# ProPrj_W51F6240S16_DEVB_V2_2026-07-19.net
KiCad netlist of a schematic drawn in EasyEDA Pro
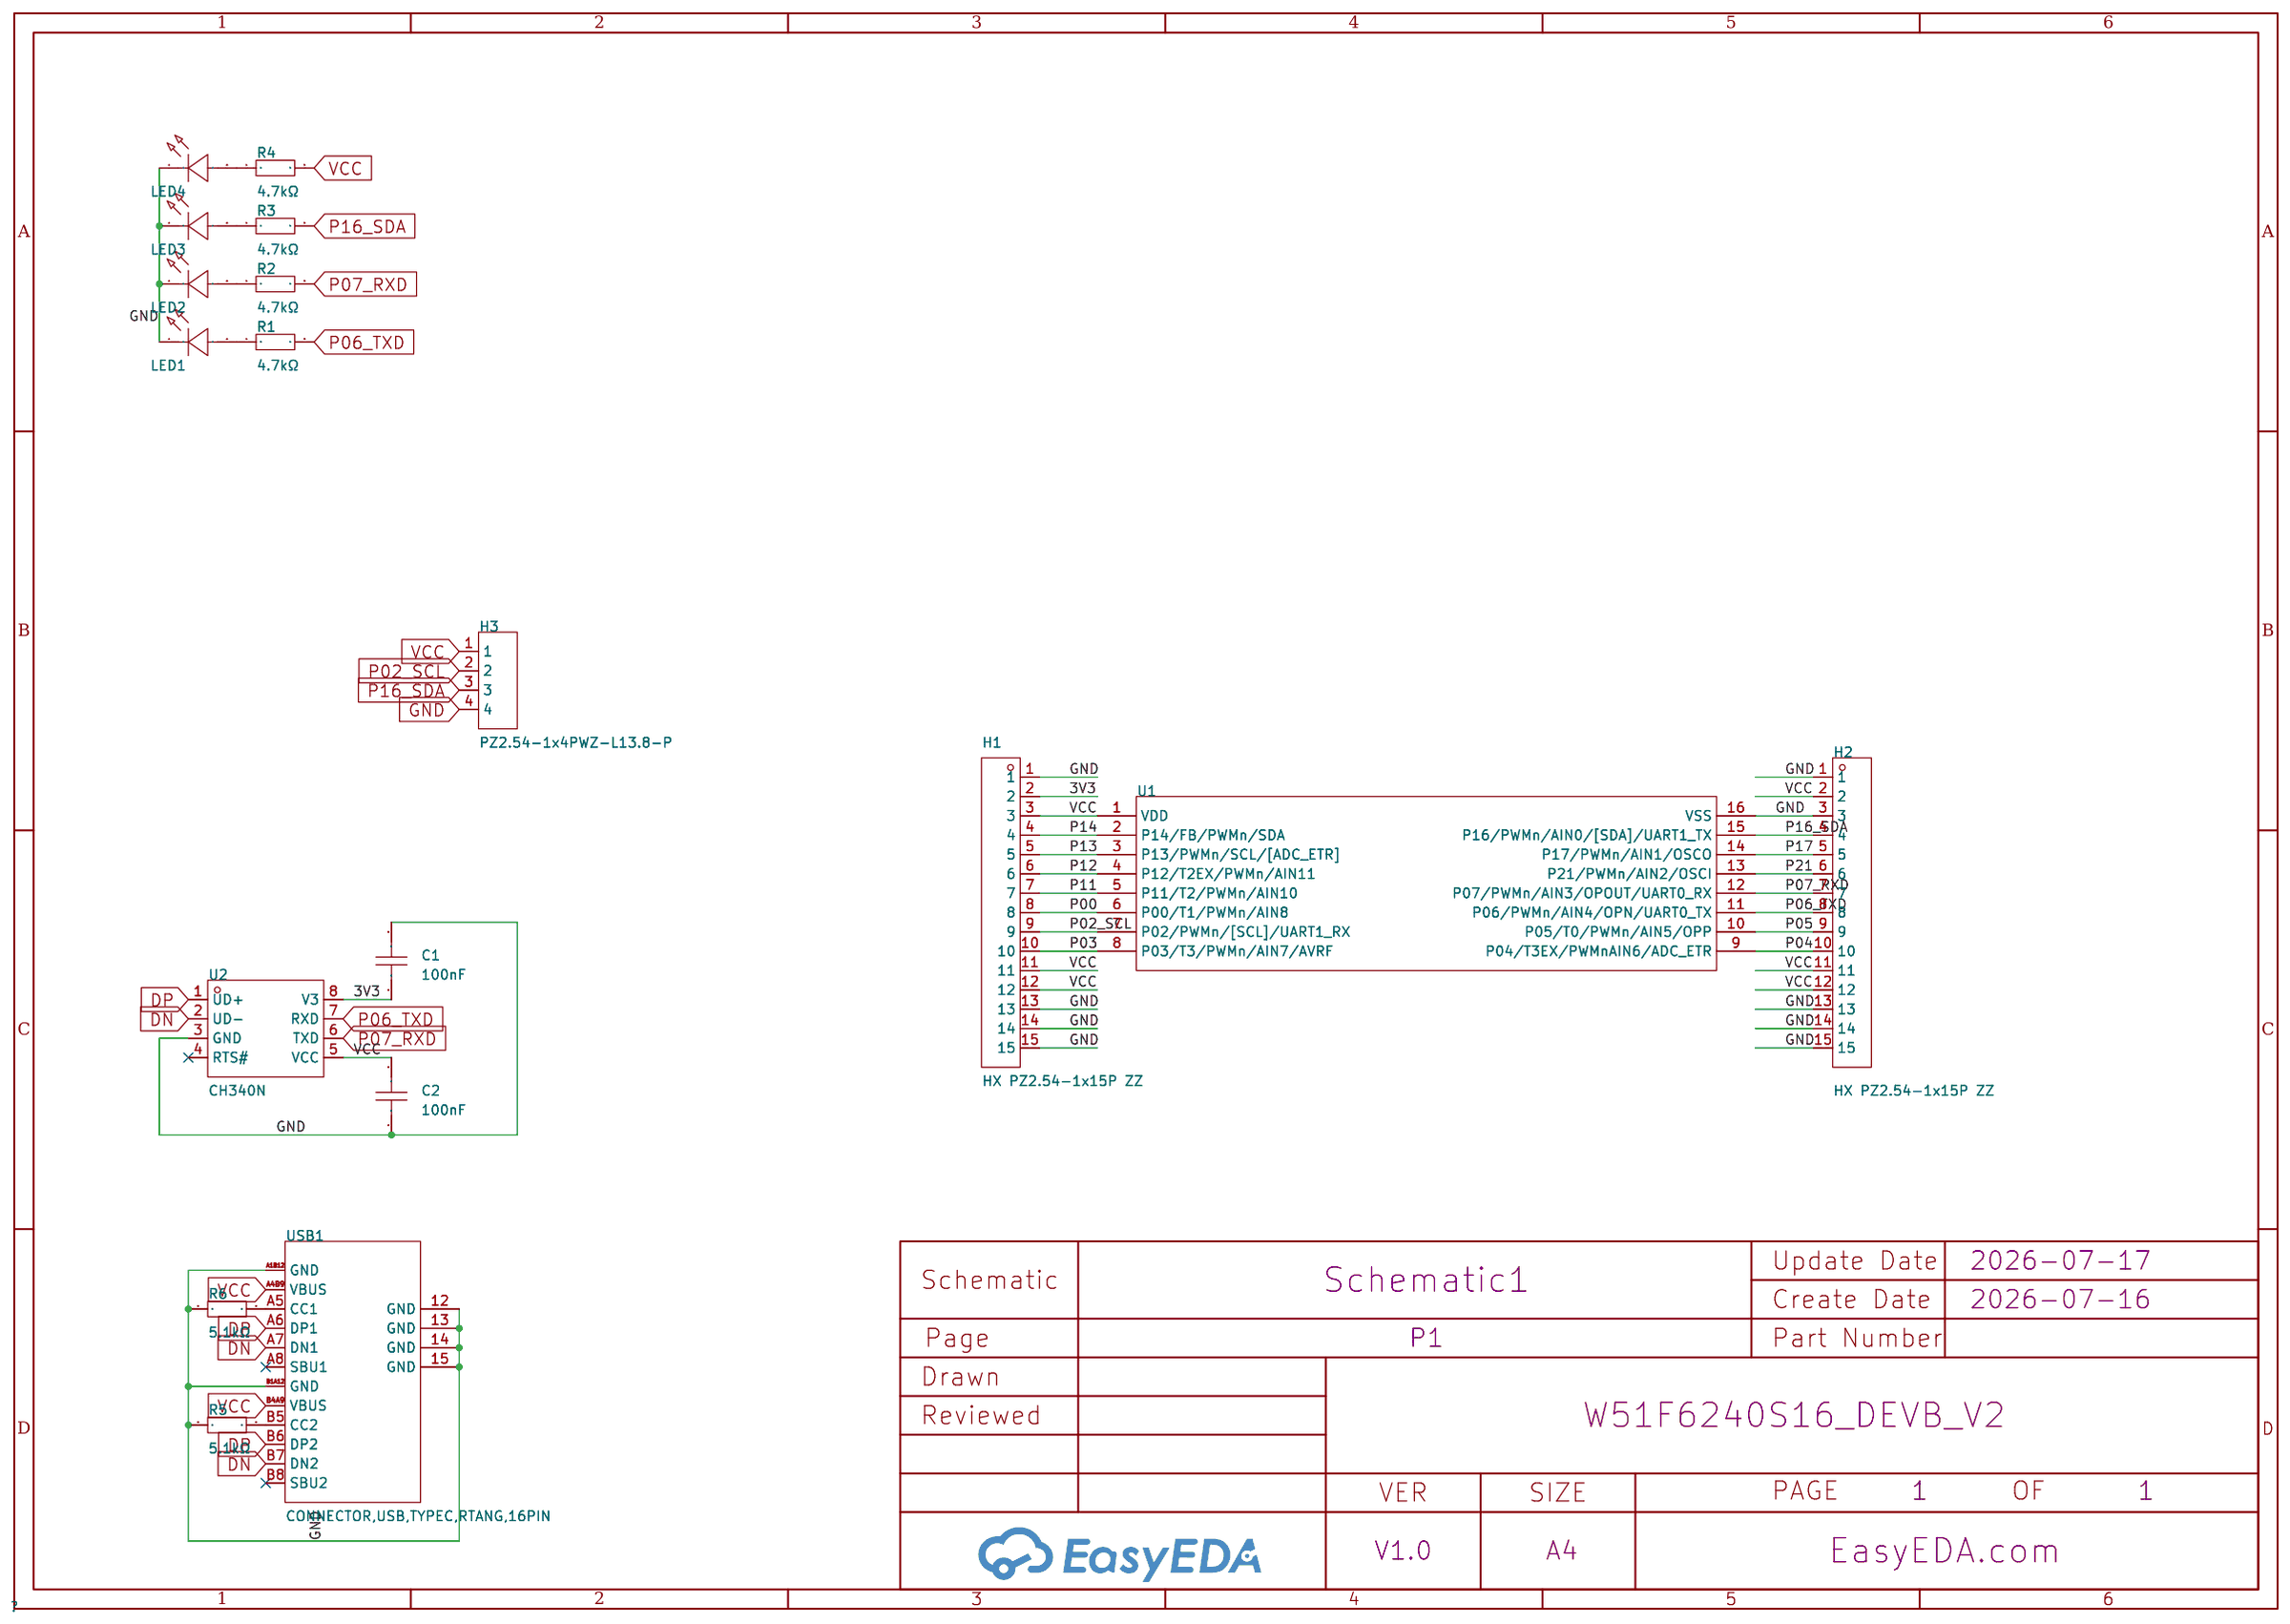
[diagram p0: schematic sheet]

(export (version "E")
  (design (tool "Eeschema 10.0.6"))
  (components
    (comp (ref "C1")
      (value "100nF")
      (footprint "easyedapro:C1206")
      (description "Capacitance:100nF Tolerance:±5% Tolerance:±5% Voltage Rating:50V Temperature Coefficient:C0G")
      (fields (field (name "Manufacturer Part") "FN31N104J500EPG") (field (name "Manufacturer") "PSA(信昌电陶)"))
      (libsource (lib "easyedapro") (part "FN31N104J500EPG"))
    )
    (comp (ref "C2")
      (value "100nF")
      (footprint "easyedapro:C1206")
      (description "Capacitance:100nF Tolerance:±5% Tolerance:±5% Voltage Rating:50V Temperature Coefficient:C0G")
      (fields (field (name "Manufacturer Part") "FN31N104J500EPG") (field (name "Manufacturer") "PSA(信昌电陶)"))
      (libsource (lib "easyedapro") (part "FN31N104J500EPG"))
    )
    (comp (ref "H1")
      (value "HX PZ2.54-1x15P ZZ")
      (footprint "easyedapro:HDR-TH_15P-P2.54-V-M")
      (fields (field (name "Manufacturer") "hanxia(韩下)"))
      (libsource (lib "easyedapro") (part "HX PZ2.54-1X15P ZZ"))
    )
    (comp (ref "H2")
      (value "HX PZ2.54-1x15P ZZ")
      (footprint "easyedapro:HDR-TH_15P-P2.54-V-M")
      (fields (field (name "Manufacturer") "hanxia(韩下)"))
      (libsource (lib "easyedapro") (part "HX PZ2.54-1X15P ZZ"))
    )
    (comp (ref "H3")
      (value "PZ2.54-1x4PWZ-L13.8-P")
      (footprint "easyedapro:HDR-TH_4P-P2.54-H-M-W7.7-P")
      (fields (field (name "Manufacturer") "SHOU HAN(首韩)"))
      (libsource (lib "easyedapro") (part "PZ2.54-1X4PWZ-L13.8-P"))
    )
    (comp (ref "LED1")
      (value "LED1206")
      (footprint "easyedapro:LED1206-RD")
      (libsource (lib "easyedapro") (part "LED1206"))
    )
    (comp (ref "LED2")
      (value "LED1206")
      (footprint "easyedapro:LED1206-RD")
      (libsource (lib "easyedapro") (part "LED1206"))
    )
    (comp (ref "LED3")
      (value "LED1206")
      (footprint "easyedapro:LED1206-RD")
      (libsource (lib "easyedapro") (part "LED1206"))
    )
    (comp (ref "LED4")
      (value "LED1206")
      (footprint "easyedapro:LED1206-RD")
      (libsource (lib "easyedapro") (part "LED1206"))
    )
    (comp (ref "R1")
      (value "4.7kΩ")
      (footprint "easyedapro:R1206")
      (fields (field (name "Manufacturer Part") "RS-06K472FT") (field (name "Manufacturer") "FH(风华)"))
      (libsource (lib "easyedapro") (part "RS-06K472FT"))
    )
    (comp (ref "R2")
      (value "4.7kΩ")
      (footprint "easyedapro:R1206")
      (fields (field (name "Manufacturer Part") "RS-06K472FT") (field (name "Manufacturer") "FH(风华)"))
      (libsource (lib "easyedapro") (part "RS-06K472FT"))
    )
    (comp (ref "R3")
      (value "4.7kΩ")
      (footprint "easyedapro:R1206")
      (fields (field (name "Manufacturer Part") "RS-06K472FT") (field (name "Manufacturer") "FH(风华)"))
      (libsource (lib "easyedapro") (part "RS-06K472FT"))
    )
    (comp (ref "R4")
      (value "4.7kΩ")
      (footprint "easyedapro:R1206")
      (fields (field (name "Manufacturer Part") "RS-06K472FT") (field (name "Manufacturer") "FH(风华)"))
      (libsource (lib "easyedapro") (part "RS-06K472FT"))
    )
    (comp (ref "R5")
      (value "5.1kΩ")
      (footprint "easyedapro:R1206")
      (fields (field (name "Manufacturer Part") "AC1206FR-075K1L") (field (name "Manufacturer") "YAGEO(国巨)"))
      (libsource (lib "easyedapro") (part "AC1206FR-075K1L"))
    )
    (comp (ref "R6")
      (value "5.1kΩ")
      (footprint "easyedapro:R1206")
      (fields (field (name "Manufacturer Part") "AC1206FR-075K1L") (field (name "Manufacturer") "YAGEO(国巨)"))
      (libsource (lib "easyedapro") (part "AC1206FR-075K1L"))
    )
    (comp (ref "U1")
      (value "~")
      (description "Low cost 1T 8051 MCU")
      (libsource (lib "easyedapro") (part "W51F6240S16"))
    )
    (comp (ref "U2")
      (value "CH340N")
      (footprint "easyedapro:SOP-8_L5.0-W4.0-P1.27-LS6.0-BL")
      (fields (field (name "Manufacturer") "WCH(南京沁恒)"))
      (libsource (lib "easyedapro") (part "CH340N"))
    )
    (comp (ref "USB1")
      (value "CONNECTOR,USB,TYPEC,RTANG,16PIN")
      (footprint "easyedapro:USB-SMD_TYPEC-16PIN")
      (libsource (lib "easyedapro") (part "CONNECTOR,USB,TYPEC,RTANG,16PIN"))
    )
  )
  (nets
    (net (code "1") (name "/3V3") (class "Default")
      (node (ref "C1") (pin "1") (pinfunction "1_1") (pintype "unspecified"))
      (node (ref "H1") (pin "2") (pinfunction "2_2") (pintype "unspecified"))
      (node (ref "U2") (pin "8") (pinfunction "V3_8") (pintype "unspecified"))
    )
    (net (code "2") (name "/P00") (class "Default")
      (node (ref "H1") (pin "8") (pinfunction "8_8") (pintype "unspecified"))
      (node (ref "U1") (pin "6") (pinfunction "P00/T1/PWMn/AIN8_6") (pintype "input"))
    )
    (net (code "3") (name "/P03") (class "Default")
      (node (ref "H1") (pin "10") (pinfunction "10_10") (pintype "unspecified"))
      (node (ref "U1") (pin "8") (pinfunction "P03/T3/PWMn/AIN7/AVRF_8") (pintype "input"))
    )
    (net (code "4") (name "/P04") (class "Default")
      (node (ref "H2") (pin "10") (pinfunction "10_10") (pintype "unspecified"))
      (node (ref "U1") (pin "9") (pinfunction "P04/T3EX/PWMnAIN6/ADC_ETR_9") (pintype "input"))
    )
    (net (code "5") (name "/P05") (class "Default")
      (node (ref "H2") (pin "9") (pinfunction "9_9") (pintype "unspecified"))
      (node (ref "U1") (pin "10") (pinfunction "P05/T0/PWMn/AIN5/OPP_10") (pintype "input"))
    )
    (net (code "6") (name "/P11") (class "Default")
      (node (ref "H1") (pin "7") (pinfunction "7_7") (pintype "unspecified"))
      (node (ref "U1") (pin "5") (pinfunction "P11/T2/PWMn/AIN10_5") (pintype "input"))
    )
    (net (code "7") (name "/P12") (class "Default")
      (node (ref "H1") (pin "6") (pinfunction "6_6") (pintype "unspecified"))
      (node (ref "U1") (pin "4") (pinfunction "P12/T2EX/PWMn/AIN11_4") (pintype "input"))
    )
    (net (code "8") (name "/P13") (class "Default")
      (node (ref "H1") (pin "5") (pinfunction "5_5") (pintype "unspecified"))
      (node (ref "U1") (pin "3") (pinfunction "P13/PWMn/SCL/[ADC_ETR]_3") (pintype "input"))
    )
    (net (code "9") (name "/P14") (class "Default")
      (node (ref "H1") (pin "4") (pinfunction "4_4") (pintype "unspecified"))
      (node (ref "U1") (pin "2") (pinfunction "P14/FB/PWMn/SDA_2") (pintype "input"))
    )
    (net (code "10") (name "/P17") (class "Default")
      (node (ref "H2") (pin "5") (pinfunction "5_5") (pintype "unspecified"))
      (node (ref "U1") (pin "14") (pinfunction "P17/PWMn/AIN1/OSCO_14") (pintype "input"))
    )
    (net (code "11") (name "/P21") (class "Default")
      (node (ref "H2") (pin "6") (pinfunction "6_6") (pintype "unspecified"))
      (node (ref "U1") (pin "13") (pinfunction "P21/PWMn/AIN2/OSCI_13") (pintype "input"))
    )
    (net (code "12") (name "DN") (class "Default")
      (node (ref "U2") (pin "2") (pinfunction "UD-_2") (pintype "unspecified"))
      (node (ref "USB1") (pin "A7") (pinfunction "DN1_A7") (pintype "unspecified"))
      (node (ref "USB1") (pin "B7") (pinfunction "DN2_B7") (pintype "unspecified"))
    )
    (net (code "13") (name "DP") (class "Default")
      (node (ref "U2") (pin "1") (pinfunction "UD+_1") (pintype "unspecified"))
      (node (ref "USB1") (pin "A6") (pinfunction "DP1_A6") (pintype "unspecified"))
      (node (ref "USB1") (pin "B6") (pinfunction "DP2_B6") (pintype "unspecified"))
    )
    (net (code "14") (name "GND") (class "Default")
      (node (ref "C1") (pin "2") (pinfunction "2_2") (pintype "unspecified"))
      (node (ref "C2") (pin "1") (pinfunction "1_1") (pintype "unspecified"))
      (node (ref "H1") (pin "1") (pinfunction "1_1") (pintype "unspecified"))
      (node (ref "H1") (pin "13") (pinfunction "13_13") (pintype "unspecified"))
      (node (ref "H1") (pin "14") (pinfunction "14_14") (pintype "unspecified"))
      (node (ref "H1") (pin "15") (pinfunction "15_15") (pintype "unspecified"))
      (node (ref "H2") (pin "1") (pinfunction "1_1") (pintype "unspecified"))
      (node (ref "H2") (pin "13") (pinfunction "13_13") (pintype "unspecified"))
      (node (ref "H2") (pin "14") (pinfunction "14_14") (pintype "unspecified"))
      (node (ref "H2") (pin "15") (pinfunction "15_15") (pintype "unspecified"))
      (node (ref "H2") (pin "3") (pinfunction "3_3") (pintype "unspecified"))
      (node (ref "H3") (pin "4") (pinfunction "4_4") (pintype "unspecified"))
      (node (ref "LED1") (pin "1") (pinfunction "K_1") (pintype "input"))
      (node (ref "LED2") (pin "1") (pinfunction "K_1") (pintype "input"))
      (node (ref "LED3") (pin "1") (pinfunction "K_1") (pintype "input"))
      (node (ref "LED4") (pin "1") (pinfunction "K_1") (pintype "input"))
      (node (ref "R5") (pin "1") (pinfunction "1_1") (pintype "unspecified"))
      (node (ref "R6") (pin "1") (pinfunction "1_1") (pintype "unspecified"))
      (node (ref "U1") (pin "16") (pinfunction "VSS_16") (pintype "input"))
      (node (ref "U2") (pin "3") (pinfunction "GND_3") (pintype "unspecified"))
      (node (ref "USB1") (pin "12") (pinfunction "GND_12") (pintype "unspecified"))
      (node (ref "USB1") (pin "13") (pinfunction "GND_13") (pintype "unspecified"))
      (node (ref "USB1") (pin "14") (pinfunction "GND_14") (pintype "unspecified"))
      (node (ref "USB1") (pin "15") (pinfunction "GND_15") (pintype "unspecified"))
      (node (ref "USB1") (pin "A1B12") (pinfunction "GND_A1B12") (pintype "unspecified"))
      (node (ref "USB1") (pin "B1A12") (pinfunction "GND_B1A12") (pintype "unspecified"))
    )
    (net (code "15") (name "Net-(LED1-A)") (class "Default")
      (node (ref "LED1") (pin "2") (pinfunction "A_2") (pintype "input"))
      (node (ref "R1") (pin "1") (pinfunction "1_1") (pintype "unspecified"))
    )
    (net (code "16") (name "Net-(LED2-A)") (class "Default")
      (node (ref "LED2") (pin "2") (pinfunction "A_2") (pintype "input"))
      (node (ref "R2") (pin "1") (pinfunction "1_1") (pintype "unspecified"))
    )
    (net (code "17") (name "Net-(LED3-A)") (class "Default")
      (node (ref "LED3") (pin "2") (pinfunction "A_2") (pintype "input"))
      (node (ref "R3") (pin "1") (pinfunction "1_1") (pintype "unspecified"))
    )
    (net (code "18") (name "Net-(LED4-A)") (class "Default")
      (node (ref "LED4") (pin "2") (pinfunction "A_2") (pintype "input"))
      (node (ref "R4") (pin "1") (pinfunction "1_1") (pintype "unspecified"))
    )
    (net (code "19") (name "Net-(USB1-CC1)") (class "Default")
      (node (ref "R6") (pin "2") (pinfunction "2_2") (pintype "unspecified"))
      (node (ref "USB1") (pin "A5") (pinfunction "CC1_A5") (pintype "unspecified"))
    )
    (net (code "20") (name "Net-(USB1-CC2)") (class "Default")
      (node (ref "R5") (pin "2") (pinfunction "2_2") (pintype "unspecified"))
      (node (ref "USB1") (pin "B5") (pinfunction "CC2_B5") (pintype "unspecified"))
    )
    (net (code "21") (name "P02_SCL") (class "Default")
      (node (ref "H1") (pin "9") (pinfunction "9_9") (pintype "unspecified"))
      (node (ref "H3") (pin "2") (pinfunction "2_2") (pintype "unspecified"))
      (node (ref "U1") (pin "7") (pinfunction "P02/PWMn/[SCL]/UART1_RX_7") (pintype "input"))
    )
    (net (code "22") (name "P06_TXD") (class "Default")
      (node (ref "H2") (pin "8") (pinfunction "8_8") (pintype "unspecified"))
      (node (ref "R1") (pin "2") (pinfunction "2_2") (pintype "unspecified"))
      (node (ref "U1") (pin "11") (pinfunction "P06/PWMn/AIN4/OPN/UART0_TX_11") (pintype "input"))
      (node (ref "U2") (pin "7") (pinfunction "RXD_7") (pintype "unspecified"))
    )
    (net (code "23") (name "P07_RXD") (class "Default")
      (node (ref "H2") (pin "7") (pinfunction "7_7") (pintype "unspecified"))
      (node (ref "R2") (pin "2") (pinfunction "2_2") (pintype "unspecified"))
      (node (ref "U1") (pin "12") (pinfunction "P07/PWMn/AIN3/OPOUT/UART0_RX_12") (pintype "input"))
      (node (ref "U2") (pin "6") (pinfunction "TXD_6") (pintype "unspecified"))
    )
    (net (code "24") (name "P16_SDA") (class "Default")
      (node (ref "H2") (pin "4") (pinfunction "4_4") (pintype "unspecified"))
      (node (ref "H3") (pin "3") (pinfunction "3_3") (pintype "unspecified"))
      (node (ref "R3") (pin "2") (pinfunction "2_2") (pintype "unspecified"))
      (node (ref "U1") (pin "15") (pinfunction "P16/PWMn/AIN0/[SDA]/UART1_TX_15") (pintype "input"))
    )
    (net (code "25") (name "VCC") (class "Default")
      (node (ref "C2") (pin "2") (pinfunction "2_2") (pintype "unspecified"))
      (node (ref "H1") (pin "11") (pinfunction "11_11") (pintype "unspecified"))
      (node (ref "H1") (pin "12") (pinfunction "12_12") (pintype "unspecified"))
      (node (ref "H1") (pin "3") (pinfunction "3_3") (pintype "unspecified"))
      (node (ref "H2") (pin "11") (pinfunction "11_11") (pintype "unspecified"))
      (node (ref "H2") (pin "12") (pinfunction "12_12") (pintype "unspecified"))
      (node (ref "H2") (pin "2") (pinfunction "2_2") (pintype "unspecified"))
      (node (ref "H3") (pin "1") (pinfunction "1_1") (pintype "unspecified"))
      (node (ref "R4") (pin "2") (pinfunction "2_2") (pintype "unspecified"))
      (node (ref "U1") (pin "1") (pinfunction "VDD_1") (pintype "input"))
      (node (ref "U2") (pin "5") (pinfunction "VCC_5") (pintype "unspecified"))
      (node (ref "USB1") (pin "A4B9") (pinfunction "VBUS_A4B9") (pintype "unspecified"))
      (node (ref "USB1") (pin "B4A9") (pinfunction "VBUS_B4A9") (pintype "unspecified"))
    )
    (net (code "26") (name "unconnected-(U2-RTS#-Pad4)") (class "Default")
      (node (ref "U2") (pin "4") (pinfunction "RTS#_4") (pintype "unspecified+no_connect"))
    )
    (net (code "27") (name "unconnected-(USB1-SBU1-PadA8)") (class "Default")
      (node (ref "USB1") (pin "A8") (pinfunction "SBU1_A8") (pintype "unspecified+no_connect"))
    )
    (net (code "28") (name "unconnected-(USB1-SBU2-PadB8)") (class "Default")
      (node (ref "USB1") (pin "B8") (pinfunction "SBU2_B8") (pintype "unspecified+no_connect"))
    )
  )
)
